# Relay.net
KiCad netlist of a schematic drawn in Altium Designer
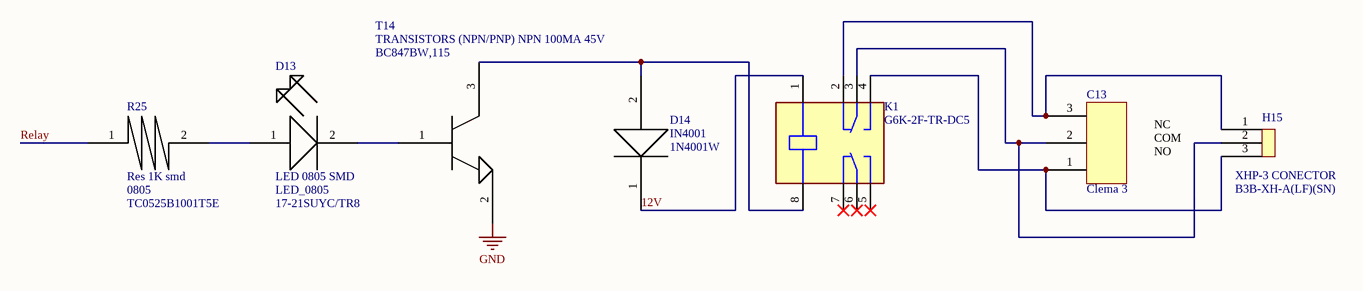
[diagram p0: Relay.SchDoc]

(export (version "E")
  (design (tool "Eeschema 10.0.6"))
  (components
    (comp (ref "C13")
      (value "Clema 3")
      (footprint "Clema3")
      (libsource (lib "Integrated_Library") (part "Clema3"))
    )
    (comp (ref "D13")
      (value "LED 0805 SMD")
      (footprint "LED SMD Amarillo")
      (description "LED 0805 Yellow")
      (fields (field (name "PACKAGE") "LED_0805") (field (name "MFR.PART #") "17-21SUYC/TR8"))
      (libsource (lib "Integrated_Library") (part "LED 0805 SMD"))
    )
    (comp (ref "D14")
      (value "IN4001")
      (footprint "C162732")
      (description "DIODES - GENERAL PURPOSE 50V 1A 1.1V @ 1A SOD-123F ROHS")
      (fields (field (name "PACKAGE PART") "SOD-123") (field (name "SUPPLIER NUMBER PART") "1N4001W"))
      (libsource (lib "Practica 1") (part "C162732"))
    )
    (comp (ref "H15")
      (value "XHP-3 CONECTOR")
      (footprint "CONECTOR XHP-3")
      (description "CONECTOR JST-XH 3 PINES")
      (fields (field (name "SUPPLIER NUMBER PART") "B3B-XH-A(LF)(SN)"))
      (libsource (lib "Practica 1") (part "B3B-XH-A(LF)(SN)"))
    )
    (comp (ref "K1")
      (value "G6K-2F-TR-DC5")
      (footprint "RELAY_G6K-2F-TR-DC5")
      (description "Telecom Relay DPDT (2 Form C) Surface Mount")
      (fields (field (name "MF") "Omron Electronics"))
      (libsource (lib "G6K-2F-TR-DC5") (part "G6K-2F-TR-DC5"))
    )
    (comp (ref "R25")
      (value "Res 1K smd")
      (footprint "RES 1K")
      (fields (field (name "PACKAGE") "0805") (field (name "MFR.PART #") "TC0525B1001T5E"))
      (libsource (lib "Integrated_Library") (part "Res 1K smd"))
    )
    (comp (ref "T14")
      (value "TRANSISTORS (NPN/PNP) NPN 100MA 45V")
      (footprint "C8659")
      (description "TRANSISTORS (NPN/PNP) NPN 100MA 45V SOT-323(SC-70) ROHS")
      (fields (field (name "PACKAGE PART") "SOT-323-3") (field (name "SUPPLIER NUMBER PART") "BC847BW,115"))
      (libsource (lib "Practica 1") (part "C8659"))
    )
  )
  (nets
    (net (code "1") (name "/12V") (class "Default")
      (node (ref "D14") (pin "1") (pinfunction "1_1") (pintype "passive"))
      (node (ref "K1") (pin "1") (pinfunction "1_1") (pintype "passive"))
    )
    (net (code "2") (name "/Relay") (class "Default")
      (node (ref "R25") (pin "1") (pinfunction "1_1") (pintype "passive"))
    )
    (net (code "3") (name "GND") (class "Default")
      (node (ref "T14") (pin "2") (pinfunction "2_2") (pintype "passive"))
    )
    (net (code "4") (name "Net-(C13-Pad1)") (class "Default")
      (node (ref "C13") (pin "1") (pinfunction "1_1") (pintype "passive"))
      (node (ref "H15") (pin "3") (pinfunction "3_3") (pintype "passive"))
      (node (ref "K1") (pin "4") (pinfunction "4_4") (pintype "passive"))
    )
    (net (code "5") (name "Net-(C13-Pad2)") (class "Default")
      (node (ref "C13") (pin "2") (pinfunction "2_2") (pintype "passive"))
      (node (ref "H15") (pin "2") (pinfunction "2_2") (pintype "passive"))
      (node (ref "K1") (pin "3") (pinfunction "3_3") (pintype "passive"))
    )
    (net (code "6") (name "Net-(C13-Pad3)") (class "Default")
      (node (ref "C13") (pin "3") (pinfunction "3_3") (pintype "passive"))
      (node (ref "H15") (pin "1") (pinfunction "1_1") (pintype "passive"))
      (node (ref "K1") (pin "2") (pinfunction "2_2") (pintype "passive"))
    )
    (net (code "7") (name "Net-(D13-Pad1)") (class "Default")
      (node (ref "D13") (pin "1") (pinfunction "1_1") (pintype "passive"))
      (node (ref "R25") (pin "2") (pinfunction "2_2") (pintype "passive"))
    )
    (net (code "8") (name "Net-(D13-Pad2)") (class "Default")
      (node (ref "D13") (pin "2") (pinfunction "2_2") (pintype "passive"))
      (node (ref "T14") (pin "1") (pinfunction "1_1") (pintype "passive"))
    )
    (net (code "9") (name "Net-(D14-Pad2)") (class "Default")
      (node (ref "D14") (pin "2") (pinfunction "2_2") (pintype "passive"))
      (node (ref "K1") (pin "8") (pinfunction "8_8") (pintype "passive"))
      (node (ref "T14") (pin "3") (pinfunction "3_3") (pintype "passive"))
    )
    (net (code "10") (name "unconnected-(K1-Pad5)") (class "Default")
      (node (ref "K1") (pin "5") (pinfunction "5_5") (pintype "passive+no_connect"))
    )
    (net (code "11") (name "unconnected-(K1-Pad6)") (class "Default")
      (node (ref "K1") (pin "6") (pinfunction "6_6") (pintype "passive+no_connect"))
    )
    (net (code "12") (name "unconnected-(K1-Pad7)") (class "Default")
      (node (ref "K1") (pin "7") (pinfunction "7_7") (pintype "passive+no_connect"))
    )
  )
)
